# RPi_Rover_Hat.net
KiCad netlist of a schematic drawn in EAGLE
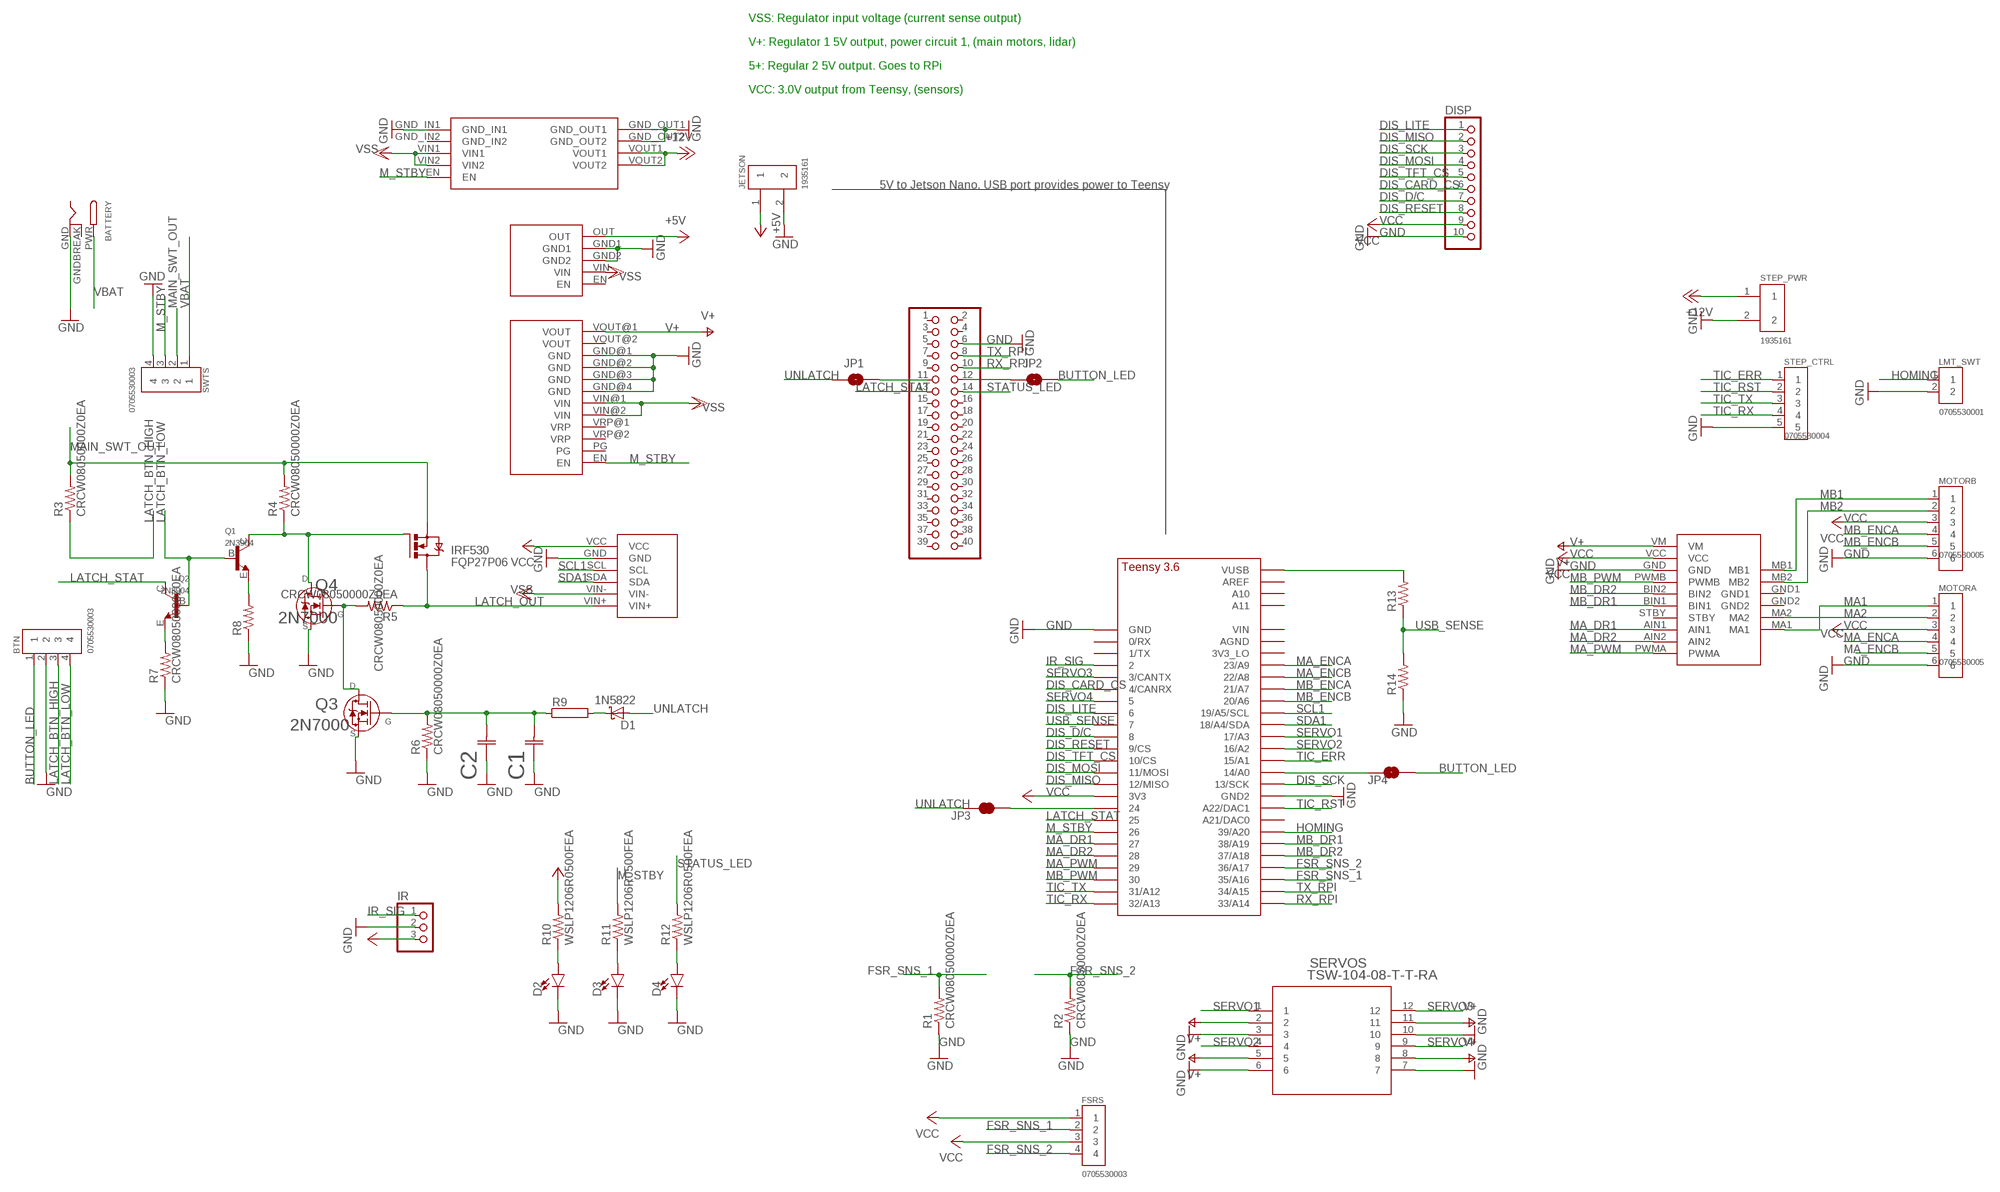
[diagram p0: schematic, sheet 1]

(export (version "E")
  (design (tool "Eeschema 10.0.6"))
  (components
    (comp (ref "BATTERY")
      (value "DCBARRELPTH")
      (footprint "eagle-import:DCJACK_2MM_PTH")
      (libsource (lib "eagle-import") (part "DCBARRELPTH"))
    )
    (comp (ref "BTN")
      (value "0705530003")
      (footprint "eagle-import:MOLEX_0705530003")
      (fields (field (name "DIGI-KEY_PART_NUMBER") "WM4902-ND") (field (name "MF") "Molex"))
      (libsource (lib "eagle-import") (part "0705530003"))
    )
    (comp (ref "C1")
      (value "FK24X5R0J226M")
      (footprint "eagle-import:CAP_R4525B")
      (libsource (lib "eagle-import") (part "FK24X5R0J226M"))
    )
    (comp (ref "C2")
      (value "FK24X5R0J226M")
      (footprint "eagle-import:CAP_R4525B")
      (libsource (lib "eagle-import") (part "FK24X5R0J226M"))
    )
    (comp (ref "D1")
      (value "1N5822")
      (footprint "eagle-import:DIOAD2120W130L950D530P")
      (fields (field (name "DIGI-KEY_PART_NUMBER") "1N5822FSCT-ND") (field (name "MF") "ON Semiconductor"))
      (libsource (lib "eagle-import") (part "1N5822"))
    )
    (comp (ref "D2")
      (value "LED1206")
      (footprint "eagle-import:LED-1206")
      (libsource (lib "eagle-import") (part "LED1206"))
    )
    (comp (ref "D3")
      (value "LED1206")
      (footprint "eagle-import:LED-1206")
      (libsource (lib "eagle-import") (part "LED1206"))
    )
    (comp (ref "D4")
      (value "LED1206")
      (footprint "eagle-import:LED-1206")
      (libsource (lib "eagle-import") (part "LED1206"))
    )
    (comp (ref "DISP")
      (value "PINHD-1X10")
      (footprint "eagle-import:1X10")
      (libsource (lib "eagle-import") (part "PINHD-1X10"))
    )
    (comp (ref "FQP27P06")
      (value "IRF530")
      (footprint "eagle-import:TO220BV")
      (fields (field (name "MF") "Vishay Siliconix"))
      (libsource (lib "eagle-import") (part "IRF530"))
    )
    (comp (ref "FSRS")
      (value "0705530003")
      (footprint "eagle-import:MOLEX_0705530003")
      (fields (field (name "DIGI-KEY_PART_NUMBER") "WM4902-ND") (field (name "MF") "Molex"))
      (libsource (lib "eagle-import") (part "0705530003"))
    )
    (comp (ref "IR")
      (value "PINHD-1X3")
      (footprint "eagle-import:1X03")
      (libsource (lib "eagle-import") (part "PINHD-1X3"))
    )
    (comp (ref "JETSON")
      (value "1935161")
      (footprint "eagle-import:PHOENIX_1935161")
      (fields (field (name "DIGI-KEY_PART_NUMBER") "277-1667-ND") (field (name "MF") "Phoenix Contact"))
      (libsource (lib "eagle-import") (part "1935161"))
    )
    (comp (ref "JP1")
      (value "JUMPER-SMT_2_NO_NO-SILK")
      (footprint "eagle-import:SMT-JUMPER_2_NO_NO-SILK")
      (libsource (lib "eagle-import") (part "JUMPER-SMT_2_NO_NO-SILK"))
    )
    (comp (ref "JP2")
      (value "JUMPER-SMT_2_NO_NO-SILK")
      (footprint "eagle-import:SMT-JUMPER_2_NO_NO-SILK")
      (libsource (lib "eagle-import") (part "JUMPER-SMT_2_NO_NO-SILK"))
    )
    (comp (ref "JP3")
      (value "JUMPER-SMT_2_NC_TRACE_NO-SILK")
      (footprint "eagle-import:SMT-JUMPER_2_NC_TRACE_NO-SILK")
      (libsource (lib "eagle-import") (part "JUMPER-SMT_2_NC_TRACE_NO-SILK"))
    )
    (comp (ref "JP4")
      (value "JUMPER-SMT_2_NC_TRACE_NO-SILK")
      (footprint "eagle-import:SMT-JUMPER_2_NC_TRACE_NO-SILK")
      (libsource (lib "eagle-import") (part "JUMPER-SMT_2_NC_TRACE_NO-SILK"))
    )
    (comp (ref "LMT_SWT")
      (value "0705530001")
      (footprint "eagle-import:MOLEX_0705530001")
      (libsource (lib "eagle-import") (part "0705530001"))
    )
    (comp (ref "MAIN_HEADER")
      (value "PINHD-2X20")
      (footprint "eagle-import:2X20")
      (libsource (lib "eagle-import") (part "PINHD-2X20"))
    )
    (comp (ref "MOTORA")
      (value "0705530005")
      (footprint "eagle-import:MOLEX_0705530005")
      (libsource (lib "eagle-import") (part "0705530005"))
    )
    (comp (ref "MOTORB")
      (value "0705530005")
      (footprint "eagle-import:MOLEX_0705530005")
      (libsource (lib "eagle-import") (part "0705530005"))
    )
    (comp (ref "Q1")
      (value "2N3904")
      (footprint "eagle-import:TO92")
      (libsource (lib "eagle-import") (part "2N3904"))
    )
    (comp (ref "Q2")
      (value "2N3904")
      (footprint "eagle-import:TO92")
      (libsource (lib "eagle-import") (part "2N3904"))
    )
    (comp (ref "Q3")
      (value "2N7000")
      (footprint "eagle-import:TO-92")
      (libsource (lib "eagle-import") (part "2N7000"))
    )
    (comp (ref "Q4")
      (value "2N7000")
      (footprint "eagle-import:TO-92")
      (libsource (lib "eagle-import") (part "2N7000"))
    )
    (comp (ref "R1")
      (value "CRCW08050000Z0EA")
      (footprint "eagle-import:RES_0805")
      (fields
        (field (name "DIGIKEY_PART_NUMBER") "541-0.0ATR-ND")
        (field (name "MANUFACTURER") "Vishay Dale")
        (field (name "CREATED_BY") "PCBLayout.com")
      )
      (libsource (lib "eagle-import") (part "CRCW08050000Z0EA"))
    )
    (comp (ref "R2")
      (value "CRCW08050000Z0EA")
      (footprint "eagle-import:RES_0805")
      (fields
        (field (name "DIGIKEY_PART_NUMBER") "541-0.0ATR-ND")
        (field (name "MANUFACTURER") "Vishay Dale")
        (field (name "CREATED_BY") "PCBLayout.com")
      )
      (libsource (lib "eagle-import") (part "CRCW08050000Z0EA"))
    )
    (comp (ref "R3")
      (value "CRCW08050000Z0EA")
      (footprint "eagle-import:RES_0805")
      (fields
        (field (name "DIGIKEY_PART_NUMBER") "541-0.0ATR-ND")
        (field (name "MANUFACTURER") "Vishay Dale")
        (field (name "CREATED_BY") "PCBLayout.com")
      )
      (libsource (lib "eagle-import") (part "CRCW08050000Z0EA"))
    )
    (comp (ref "R4")
      (value "CRCW08050000Z0EA")
      (footprint "eagle-import:RES_0805")
      (fields
        (field (name "DIGIKEY_PART_NUMBER") "541-0.0ATR-ND")
        (field (name "MANUFACTURER") "Vishay Dale")
        (field (name "CREATED_BY") "PCBLayout.com")
      )
      (libsource (lib "eagle-import") (part "CRCW08050000Z0EA"))
    )
    (comp (ref "R5")
      (value "CRCW08050000Z0EA")
      (footprint "eagle-import:RES_0805")
      (fields
        (field (name "DIGIKEY_PART_NUMBER") "541-0.0ATR-ND")
        (field (name "MANUFACTURER") "Vishay Dale")
        (field (name "CREATED_BY") "PCBLayout.com")
      )
      (libsource (lib "eagle-import") (part "CRCW08050000Z0EA"))
    )
    (comp (ref "R6")
      (value "CRCW08050000Z0EA")
      (footprint "eagle-import:RES_0805")
      (fields
        (field (name "DIGIKEY_PART_NUMBER") "541-0.0ATR-ND")
        (field (name "MANUFACTURER") "Vishay Dale")
        (field (name "CREATED_BY") "PCBLayout.com")
      )
      (libsource (lib "eagle-import") (part "CRCW08050000Z0EA"))
    )
    (comp (ref "R7")
      (value "CRCW08050000Z0EA")
      (footprint "eagle-import:RES_0805")
      (fields
        (field (name "DIGIKEY_PART_NUMBER") "541-0.0ATR-ND")
        (field (name "MANUFACTURER") "Vishay Dale")
        (field (name "CREATED_BY") "PCBLayout.com")
      )
      (libsource (lib "eagle-import") (part "CRCW08050000Z0EA"))
    )
    (comp (ref "R8")
      (value "CRCW08050000Z0EA")
      (footprint "eagle-import:RES_0805")
      (fields
        (field (name "DIGIKEY_PART_NUMBER") "541-0.0ATR-ND")
        (field (name "MANUFACTURER") "Vishay Dale")
        (field (name "CREATED_BY") "PCBLayout.com")
      )
      (libsource (lib "eagle-import") (part "CRCW08050000Z0EA"))
    )
    (comp (ref "R9")
      (value "RHPS58")
      (footprint "eagle-import:HPS58")
      (libsource (lib "eagle-import") (part "RHPS58"))
    )
    (comp (ref "R10")
      (value "WSLP1206R0500FEA")
      (footprint "eagle-import:RES_1206")
      (fields
        (field (name "DIGIKEY_PART_NUMBER") "WSLP-.05TR-ND")
        (field (name "MANUFACTURER") "Vishay Dale")
        (field (name "CREATED_BY") "PCBLayout.com")
      )
      (libsource (lib "eagle-import") (part "WSLP1206R0500FEA"))
    )
    (comp (ref "R11")
      (value "WSLP1206R0500FEA")
      (footprint "eagle-import:RES_1206")
      (fields
        (field (name "DIGIKEY_PART_NUMBER") "WSLP-.05TR-ND")
        (field (name "MANUFACTURER") "Vishay Dale")
        (field (name "CREATED_BY") "PCBLayout.com")
      )
      (libsource (lib "eagle-import") (part "WSLP1206R0500FEA"))
    )
    (comp (ref "R12")
      (value "WSLP1206R0500FEA")
      (footprint "eagle-import:RES_1206")
      (fields
        (field (name "DIGIKEY_PART_NUMBER") "WSLP-.05TR-ND")
        (field (name "MANUFACTURER") "Vishay Dale")
        (field (name "CREATED_BY") "PCBLayout.com")
      )
      (libsource (lib "eagle-import") (part "WSLP1206R0500FEA"))
    )
    (comp (ref "R13")
      (value "CRCW08050000Z0EA")
      (footprint "eagle-import:RES_0805")
      (fields
        (field (name "DIGIKEY_PART_NUMBER") "541-0.0ATR-ND")
        (field (name "MANUFACTURER") "Vishay Dale")
        (field (name "CREATED_BY") "PCBLayout.com")
      )
      (libsource (lib "eagle-import") (part "CRCW08050000Z0EA"))
    )
    (comp (ref "R14")
      (value "CRCW08050000Z0EA")
      (footprint "eagle-import:RES_0805")
      (fields
        (field (name "DIGIKEY_PART_NUMBER") "541-0.0ATR-ND")
        (field (name "MANUFACTURER") "Vishay Dale")
        (field (name "CREATED_BY") "PCBLayout.com")
      )
      (libsource (lib "eagle-import") (part "CRCW08050000Z0EA"))
    )
    (comp (ref "SERVOS")
      (value "TSW-104-08-T-T-RA")
      (footprint "eagle-import:TSW-104-08-T-T-RA_SAI")
      (libsource (lib "eagle-import") (part "TSW-104-08-T-T-RA"))
    )
    (comp (ref "STEP_CTRL")
      (value "0705530004")
      (footprint "eagle-import:MOLEX_0705530004")
      (libsource (lib "eagle-import") (part "0705530004"))
    )
    (comp (ref "STEP_PWR")
      (value "1935161")
      (footprint "eagle-import:PHOENIX_1935161")
      (fields (field (name "DIGI-KEY_PART_NUMBER") "277-1667-ND") (field (name "MF") "Phoenix Contact"))
      (libsource (lib "eagle-import") (part "1935161"))
    )
    (comp (ref "SWTS")
      (value "0705530003")
      (footprint "eagle-import:MOLEX_0705530003")
      (fields (field (name "DIGI-KEY_PART_NUMBER") "WM4902-ND") (field (name "MF") "Molex"))
      (libsource (lib "eagle-import") (part "0705530003"))
    )
    (comp (ref "U$1")
      (value "TEENSY_3.5/3.6_BASIC")
      (footprint "eagle-import:TEENSY_3.5_3.6_BASIC")
      (libsource (lib "eagle-import") (part "TEENSY_3.5/3.6_BASIC"))
    )
    (comp (ref "U$3")
      (value "ADAFRUIT_TB6612")
      (footprint "eagle-import:ADAFRUIT_TB6612")
      (libsource (lib "eagle-import") (part "ADAFRUIT_TB6612"))
    )
    (comp (ref "U$4")
      (value "INA219")
      (footprint "eagle-import:INA219")
      (libsource (lib "eagle-import") (part "INA219"))
    )
    (comp (ref "U$5")
      (value "D24V50F5")
      (footprint "eagle-import:D24V50F5")
      (libsource (lib "eagle-import") (part "D24V50F5"))
    )
    (comp (ref "U$6")
      (value "S18V20FX")
      (footprint "eagle-import:S18V20FX")
      (libsource (lib "eagle-import") (part "S18V20FX"))
    )
    (comp (ref "U$7")
      (value "D36V50FX")
      (footprint "eagle-import:D36V50FX")
      (libsource (lib "eagle-import") (part "D36V50FX"))
    )
  )
  (nets
    (net (code "1") (name "+5V") (class "Default")
      (node (ref "JETSON") (pin "1") (pinfunction "1_1") (pintype "passive"))
      (node (ref "U$5") (pin "OUT") (pinfunction "OUT_OUT") (pintype "bidirectional"))
    )
    (net (code "2") (name "+12V") (class "Default")
      (node (ref "STEP_PWR") (pin "1") (pinfunction "1_1") (pintype "passive"))
      (node (ref "U$6") (pin "VOUT1") (pinfunction "VOUT1_VOUT1") (pintype "bidirectional"))
      (node (ref "U$6") (pin "VOUT2") (pinfunction "VOUT2_VOUT2") (pintype "bidirectional"))
    )
    (net (code "3") (name "/BUTTON_LED") (class "Default")
      (node (ref "BTN") (pin "1") (pinfunction "1_1") (pintype "passive"))
      (node (ref "JP2") (pin "2") (pinfunction "2_2") (pintype "passive"))
      (node (ref "JP4") (pin "2") (pinfunction "2_2") (pintype "passive"))
    )
    (net (code "4") (name "/DIS_CARD_CS") (class "Default")
      (node (ref "DISP") (pin "6") (pinfunction "6_6") (pintype "passive"))
      (node (ref "U$1") (pin "4/CANRX") (pinfunction "4/CANRX_4/CANRX") (pintype "bidirectional"))
    )
    (net (code "5") (name "/DIS_D{slash}C") (class "Default")
      (node (ref "DISP") (pin "7") (pinfunction "7_7") (pintype "passive"))
      (node (ref "U$1") (pin "8") (pinfunction "8_8") (pintype "bidirectional"))
    )
    (net (code "6") (name "/DIS_LITE") (class "Default")
      (node (ref "DISP") (pin "1") (pinfunction "1_1") (pintype "passive"))
      (node (ref "U$1") (pin "6") (pinfunction "6_6") (pintype "bidirectional"))
    )
    (net (code "7") (name "/DIS_MISO") (class "Default")
      (node (ref "DISP") (pin "2") (pinfunction "2_2") (pintype "passive"))
      (node (ref "U$1") (pin "12/MISO") (pinfunction "12/MISO_12/MISO") (pintype "bidirectional"))
    )
    (net (code "8") (name "/DIS_MOSI") (class "Default")
      (node (ref "DISP") (pin "4") (pinfunction "4_4") (pintype "passive"))
      (node (ref "U$1") (pin "11/MOSI") (pinfunction "11/MOSI_11/MOSI") (pintype "bidirectional"))
    )
    (net (code "9") (name "/DIS_RESET") (class "Default")
      (node (ref "DISP") (pin "8") (pinfunction "8_8") (pintype "passive"))
      (node (ref "U$1") (pin "9/CS") (pinfunction "9/CS_9/CS") (pintype "bidirectional"))
    )
    (net (code "10") (name "/DIS_SCK") (class "Default")
      (node (ref "DISP") (pin "3") (pinfunction "3_3") (pintype "passive"))
      (node (ref "U$1") (pin "13/SCK") (pinfunction "13/SCK_13/SCK") (pintype "bidirectional"))
    )
    (net (code "11") (name "/DIS_TFT_CS") (class "Default")
      (node (ref "DISP") (pin "5") (pinfunction "5_5") (pintype "passive"))
      (node (ref "U$1") (pin "10/CS") (pinfunction "10/CS_10/CS") (pintype "bidirectional"))
    )
    (net (code "12") (name "/FSR_SNS_1") (class "Default")
      (node (ref "FSRS") (pin "2") (pinfunction "2_2") (pintype "passive"))
      (node (ref "R1") (pin "2") (pinfunction "2_2") (pintype "passive"))
      (node (ref "U$1") (pin "35/A16") (pinfunction "35/A16_35/A16") (pintype "bidirectional"))
    )
    (net (code "13") (name "/FSR_SNS_2") (class "Default")
      (node (ref "FSRS") (pin "4") (pinfunction "4_4") (pintype "passive"))
      (node (ref "R2") (pin "2") (pinfunction "2_2") (pintype "passive"))
      (node (ref "U$1") (pin "36/A17") (pinfunction "36/A17_36/A17") (pintype "bidirectional"))
    )
    (net (code "14") (name "/GNDBREAK") (class "Default")
      (node (ref "BATTERY") (pin "GNDBREAK") (pinfunction "GNDBREAK_GNDBREAK") (pintype "power_in"))
    )
    (net (code "15") (name "/HOMING") (class "Default")
      (node (ref "LMT_SWT") (pin "1") (pinfunction "1_1") (pintype "passive"))
      (node (ref "U$1") (pin "39/A20") (pinfunction "39/A20_39/A20") (pintype "bidirectional"))
    )
    (net (code "16") (name "/IR_SIG") (class "Default")
      (node (ref "IR") (pin "1") (pinfunction "1_1") (pintype "passive"))
      (node (ref "U$1") (pin "2") (pinfunction "2_2") (pintype "bidirectional"))
    )
    (net (code "17") (name "/LATCH_BTN_HIGH") (class "Default")
      (node (ref "BTN") (pin "3") (pinfunction "3_3") (pintype "passive"))
      (node (ref "R3") (pin "1") (pinfunction "1_1") (pintype "passive"))
    )
    (net (code "18") (name "/LATCH_BTN_LOW") (class "Default")
      (node (ref "BTN") (pin "4") (pinfunction "4_4") (pintype "passive"))
      (node (ref "Q1") (pin "B") (pinfunction "B_B") (pintype "passive"))
      (node (ref "Q2") (pin "B") (pinfunction "B_B") (pintype "passive"))
    )
    (net (code "19") (name "/LATCH_OUT") (class "Default")
      (node (ref "FQP27P06") (pin "D") (pinfunction "D_D") (pintype "passive"))
      (node (ref "R5") (pin "1") (pinfunction "1_1") (pintype "passive"))
      (node (ref "U$4") (pin "VIN+") (pinfunction "VIN+_VIN+") (pintype "bidirectional"))
    )
    (net (code "20") (name "/LATCH_STAT") (class "Default")
      (node (ref "MAIN_HEADER") (pin "13") (pinfunction "13_13") (pintype "passive"))
      (node (ref "Q2") (pin "C") (pinfunction "C_C") (pintype "passive"))
      (node (ref "U$1") (pin "25") (pinfunction "25_25") (pintype "bidirectional"))
    )
    (net (code "21") (name "/MA1") (class "Default")
      (node (ref "MOTORA") (pin "1") (pinfunction "1_1") (pintype "passive"))
      (node (ref "U$3") (pin "MA1") (pinfunction "MA1_MA1") (pintype "bidirectional"))
    )
    (net (code "22") (name "/MA2") (class "Default")
      (node (ref "MOTORA") (pin "2") (pinfunction "2_2") (pintype "passive"))
      (node (ref "U$3") (pin "MA2") (pinfunction "MA2_MA2") (pintype "bidirectional"))
    )
    (net (code "23") (name "/MAIN_SWT_OUT") (class "Default")
      (node (ref "FQP27P06") (pin "S") (pinfunction "S_S") (pintype "passive"))
      (node (ref "R3") (pin "2") (pinfunction "2_2") (pintype "passive"))
      (node (ref "R4") (pin "2") (pinfunction "2_2") (pintype "passive"))
      (node (ref "SWTS") (pin "2") (pinfunction "2_2") (pintype "passive"))
    )
    (net (code "24") (name "/MA_DR1") (class "Default")
      (node (ref "U$1") (pin "27") (pinfunction "27_27") (pintype "bidirectional"))
      (node (ref "U$3") (pin "AIN1") (pinfunction "AIN1_AIN1") (pintype "bidirectional"))
    )
    (net (code "25") (name "/MA_DR2") (class "Default")
      (node (ref "U$1") (pin "28") (pinfunction "28_28") (pintype "bidirectional"))
      (node (ref "U$3") (pin "AIN2") (pinfunction "AIN2_AIN2") (pintype "bidirectional"))
    )
    (net (code "26") (name "/MA_ENCA") (class "Default")
      (node (ref "MOTORA") (pin "4") (pinfunction "4_4") (pintype "passive"))
      (node (ref "U$1") (pin "23/A9") (pinfunction "23/A9_23/A9") (pintype "bidirectional"))
    )
    (net (code "27") (name "/MA_ENCB") (class "Default")
      (node (ref "MOTORA") (pin "5") (pinfunction "5_5") (pintype "passive"))
      (node (ref "U$1") (pin "22/A8") (pinfunction "22/A8_22/A8") (pintype "bidirectional"))
    )
    (net (code "28") (name "/MA_PWM") (class "Default")
      (node (ref "U$1") (pin "29") (pinfunction "29_29") (pintype "bidirectional"))
      (node (ref "U$3") (pin "PWMA") (pinfunction "PWMA_PWMA") (pintype "bidirectional"))
    )
    (net (code "29") (name "/MB1") (class "Default")
      (node (ref "MOTORB") (pin "1") (pinfunction "1_1") (pintype "passive"))
      (node (ref "U$3") (pin "MB1") (pinfunction "MB1_MB1") (pintype "bidirectional"))
    )
    (net (code "30") (name "/MB2") (class "Default")
      (node (ref "MOTORB") (pin "2") (pinfunction "2_2") (pintype "passive"))
      (node (ref "U$3") (pin "MB2") (pinfunction "MB2_MB2") (pintype "bidirectional"))
    )
    (net (code "31") (name "/MB_DR1") (class "Default")
      (node (ref "U$1") (pin "38/A19") (pinfunction "38/A19_38/A19") (pintype "bidirectional"))
      (node (ref "U$3") (pin "BIN1") (pinfunction "BIN1_BIN1") (pintype "bidirectional"))
    )
    (net (code "32") (name "/MB_DR2") (class "Default")
      (node (ref "U$1") (pin "37/A18") (pinfunction "37/A18_37/A18") (pintype "bidirectional"))
      (node (ref "U$3") (pin "BIN2") (pinfunction "BIN2_BIN2") (pintype "bidirectional"))
    )
    (net (code "33") (name "/MB_ENCA") (class "Default")
      (node (ref "MOTORB") (pin "4") (pinfunction "4_4") (pintype "passive"))
      (node (ref "U$1") (pin "21/A7") (pinfunction "21/A7_21/A7") (pintype "bidirectional"))
    )
    (net (code "34") (name "/MB_ENCB") (class "Default")
      (node (ref "MOTORB") (pin "5") (pinfunction "5_5") (pintype "passive"))
      (node (ref "U$1") (pin "20/A6") (pinfunction "20/A6_20/A6") (pintype "bidirectional"))
    )
    (net (code "35") (name "/MB_PWM") (class "Default")
      (node (ref "U$1") (pin "30") (pinfunction "30_30") (pintype "bidirectional"))
      (node (ref "U$3") (pin "PWMB") (pinfunction "PWMB_PWMB") (pintype "bidirectional"))
    )
    (net (code "36") (name "/M_STBY") (class "Default")
      (node (ref "R11") (pin "2") (pinfunction "2_2") (pintype "passive"))
      (node (ref "SWTS") (pin "3") (pinfunction "3_3") (pintype "passive"))
      (node (ref "U$1") (pin "26") (pinfunction "26_26") (pintype "bidirectional"))
      (node (ref "U$6") (pin "EN") (pinfunction "EN_EN") (pintype "bidirectional"))
      (node (ref "U$7") (pin "EN") (pinfunction "EN_EN") (pintype "bidirectional"))
    )
    (net (code "37") (name "/RX_RPI") (class "Default")
      (node (ref "MAIN_HEADER") (pin "10") (pinfunction "10_10") (pintype "passive"))
      (node (ref "U$1") (pin "33/A14") (pinfunction "33/A14_33/A14") (pintype "bidirectional"))
    )
    (net (code "38") (name "/SCL1") (class "Default")
      (node (ref "U$1") (pin "19/A5/SCL") (pinfunction "19/A5/SCL_19/A5/SCL") (pintype "bidirectional"))
      (node (ref "U$4") (pin "SCL") (pinfunction "SCL_SCL") (pintype "bidirectional"))
    )
    (net (code "39") (name "/SDA1") (class "Default")
      (node (ref "U$1") (pin "18/A4/SDA") (pinfunction "18/A4/SDA_18/A4/SDA") (pintype "bidirectional"))
      (node (ref "U$4") (pin "SDA") (pinfunction "SDA_SDA") (pintype "bidirectional"))
    )
    (net (code "40") (name "/SERVO1") (class "Default")
      (node (ref "SERVOS") (pin "1") (pinfunction "1_1") (pintype "passive"))
      (node (ref "U$1") (pin "17/A3") (pinfunction "17/A3_17/A3") (pintype "bidirectional"))
    )
    (net (code "41") (name "/SERVO2") (class "Default")
      (node (ref "SERVOS") (pin "4") (pinfunction "4_4") (pintype "passive"))
      (node (ref "U$1") (pin "16/A2") (pinfunction "16/A2_16/A2") (pintype "bidirectional"))
    )
    (net (code "42") (name "/SERVO3") (class "Default")
      (node (ref "SERVOS") (pin "12") (pinfunction "12_12") (pintype "passive"))
      (node (ref "U$1") (pin "3/CANTX") (pinfunction "3/CANTX_3/CANTX") (pintype "bidirectional"))
    )
    (net (code "43") (name "/SERVO4") (class "Default")
      (node (ref "SERVOS") (pin "9") (pinfunction "9_9") (pintype "passive"))
      (node (ref "U$1") (pin "5") (pinfunction "5_5") (pintype "bidirectional"))
    )
    (net (code "44") (name "/STATUS_LED") (class "Default")
      (node (ref "MAIN_HEADER") (pin "14") (pinfunction "14_14") (pintype "passive"))
      (node (ref "R12") (pin "2") (pinfunction "2_2") (pintype "passive"))
    )
    (net (code "45") (name "/TIC_ERR") (class "Default")
      (node (ref "STEP_CTRL") (pin "1") (pinfunction "1_1") (pintype "passive"))
      (node (ref "U$1") (pin "15/A1") (pinfunction "15/A1_15/A1") (pintype "bidirectional"))
    )
    (net (code "46") (name "/TIC_RST") (class "Default")
      (node (ref "STEP_CTRL") (pin "2") (pinfunction "2_2") (pintype "passive"))
      (node (ref "U$1") (pin "A22/DAC1") (pinfunction "A22/DAC1_A22/DAC1") (pintype "bidirectional"))
    )
    (net (code "47") (name "/TIC_RX") (class "Default")
      (node (ref "STEP_CTRL") (pin "4") (pinfunction "4_4") (pintype "passive"))
      (node (ref "U$1") (pin "32/A13") (pinfunction "32/A13_32/A13") (pintype "bidirectional"))
    )
    (net (code "48") (name "/TIC_TX") (class "Default")
      (node (ref "STEP_CTRL") (pin "3") (pinfunction "3_3") (pintype "passive"))
      (node (ref "U$1") (pin "31/A12") (pinfunction "31/A12_31/A12") (pintype "bidirectional"))
    )
    (net (code "49") (name "/TX_RPI") (class "Default")
      (node (ref "MAIN_HEADER") (pin "8") (pinfunction "8_8") (pintype "passive"))
      (node (ref "U$1") (pin "34/A15") (pinfunction "34/A15_34/A15") (pintype "bidirectional"))
    )
    (net (code "50") (name "/UNLATCH") (class "Default")
      (node (ref "D1") (pin "A") (pinfunction "A_A") (pintype "passive"))
      (node (ref "JP1") (pin "1") (pinfunction "1_1") (pintype "passive"))
      (node (ref "JP3") (pin "1") (pinfunction "1_1") (pintype "passive"))
    )
    (net (code "51") (name "/USB_SENSE") (class "Default")
      (node (ref "R13") (pin "1") (pinfunction "1_1") (pintype "passive"))
      (node (ref "R14") (pin "2") (pinfunction "2_2") (pintype "passive"))
      (node (ref "U$1") (pin "7") (pinfunction "7_7") (pintype "bidirectional"))
    )
    (net (code "52") (name "/VBAT") (class "Default")
      (node (ref "BATTERY") (pin "PWR") (pinfunction "PWR_PWR") (pintype "power_in"))
      (node (ref "SWTS") (pin "1") (pinfunction "1_1") (pintype "passive"))
    )
    (net (code "53") (name "GND") (class "Default")
      (node (ref "BATTERY") (pin "GND") (pinfunction "GND_GND") (pintype "power_in"))
      (node (ref "BTN") (pin "2") (pinfunction "2_2") (pintype "passive"))
      (node (ref "C1") (pin "1") (pinfunction "1_1") (pintype "passive"))
      (node (ref "C2") (pin "1") (pinfunction "1_1") (pintype "passive"))
      (node (ref "D2") (pin "C") (pinfunction "C_C") (pintype "passive"))
      (node (ref "D3") (pin "C") (pinfunction "C_C") (pintype "passive"))
      (node (ref "D4") (pin "C") (pinfunction "C_C") (pintype "passive"))
      (node (ref "DISP") (pin "10") (pinfunction "10_10") (pintype "passive"))
      (node (ref "IR") (pin "2") (pinfunction "2_2") (pintype "passive"))
      (node (ref "JETSON") (pin "2") (pinfunction "2_2") (pintype "passive"))
      (node (ref "LMT_SWT") (pin "2") (pinfunction "2_2") (pintype "passive"))
      (node (ref "MAIN_HEADER") (pin "6") (pinfunction "6_6") (pintype "passive"))
      (node (ref "MOTORA") (pin "6") (pinfunction "6_6") (pintype "passive"))
      (node (ref "MOTORB") (pin "6") (pinfunction "6_6") (pintype "passive"))
      (node (ref "Q3") (pin "1") (pinfunction "3_1") (pintype "passive"))
      (node (ref "Q4") (pin "1") (pinfunction "3_1") (pintype "passive"))
      (node (ref "R1") (pin "1") (pinfunction "1_1") (pintype "passive"))
      (node (ref "R14") (pin "1") (pinfunction "1_1") (pintype "passive"))
      (node (ref "R2") (pin "1") (pinfunction "1_1") (pintype "passive"))
      (node (ref "R6") (pin "1") (pinfunction "1_1") (pintype "passive"))
      (node (ref "R7") (pin "1") (pinfunction "1_1") (pintype "passive"))
      (node (ref "R8") (pin "1") (pinfunction "1_1") (pintype "passive"))
      (node (ref "SERVOS") (pin "10") (pinfunction "10_10") (pintype "passive"))
      (node (ref "SERVOS") (pin "3") (pinfunction "3_3") (pintype "passive"))
      (node (ref "SERVOS") (pin "6") (pinfunction "6_6") (pintype "passive"))
      (node (ref "SERVOS") (pin "7") (pinfunction "7_7") (pintype "passive"))
      (node (ref "STEP_CTRL") (pin "5") (pinfunction "5_5") (pintype "passive"))
      (node (ref "STEP_PWR") (pin "2") (pinfunction "2_2") (pintype "passive"))
      (node (ref "SWTS") (pin "4") (pinfunction "4_4") (pintype "passive"))
      (node (ref "U$1") (pin "GND") (pinfunction "GND_GND") (pintype "bidirectional"))
      (node (ref "U$1") (pin "GND2") (pinfunction "GND2_GND2") (pintype "bidirectional"))
      (node (ref "U$3") (pin "GND") (pinfunction "GND_GND") (pintype "bidirectional"))
      (node (ref "U$4") (pin "GND") (pinfunction "GND_GND") (pintype "bidirectional"))
      (node (ref "U$5") (pin "GND1") (pinfunction "GND1_GND1") (pintype "bidirectional"))
      (node (ref "U$5") (pin "GND2") (pinfunction "GND2_GND2") (pintype "bidirectional"))
      (node (ref "U$6") (pin "GND_IN1") (pinfunction "GND_IN1_GND_IN1") (pintype "bidirectional"))
      (node (ref "U$6") (pin "GND_OUT1") (pinfunction "GND_OUT1_GND_OUT1") (pintype "bidirectional"))
      (node (ref "U$6") (pin "GND_OUT2") (pinfunction "GND_OUT2_GND_OUT2") (pintype "bidirectional"))
      (node (ref "U$7") (pin "GND@1") (pinfunction "GND_GND@1") (pintype "bidirectional"))
      (node (ref "U$7") (pin "GND@2") (pinfunction "GND_GND@2") (pintype "bidirectional"))
      (node (ref "U$7") (pin "GND@3") (pinfunction "GND_GND@3") (pintype "bidirectional"))
      (node (ref "U$7") (pin "GND@4") (pinfunction "GND_GND@4") (pintype "bidirectional"))
    )
    (net (code "54") (name "Net-(D1-PadC)") (class "Default")
      (node (ref "D1") (pin "C") (pinfunction "C_C") (pintype "passive"))
      (node (ref "R9") (pin "2") (pinfunction "2_2") (pintype "passive"))
    )
    (net (code "55") (name "Net-(D2-PadA)") (class "Default")
      (node (ref "D2") (pin "A") (pinfunction "A_A") (pintype "passive"))
      (node (ref "R10") (pin "1") (pinfunction "1_1") (pintype "passive"))
    )
    (net (code "56") (name "Net-(D3-PadA)") (class "Default")
      (node (ref "D3") (pin "A") (pinfunction "A_A") (pintype "passive"))
      (node (ref "R11") (pin "1") (pinfunction "1_1") (pintype "passive"))
    )
    (net (code "57") (name "Net-(D4-PadA)") (class "Default")
      (node (ref "D4") (pin "A") (pinfunction "A_A") (pintype "passive"))
      (node (ref "R12") (pin "1") (pinfunction "1_1") (pintype "passive"))
    )
    (net (code "58") (name "Net-(JP1-Pad2)") (class "Default")
      (node (ref "JP1") (pin "2") (pinfunction "2_2") (pintype "passive"))
      (node (ref "MAIN_HEADER") (pin "11") (pinfunction "11_11") (pintype "passive"))
    )
    (net (code "59") (name "Net-(JP2-Pad1)") (class "Default")
      (node (ref "JP2") (pin "1") (pinfunction "1_1") (pintype "passive"))
      (node (ref "MAIN_HEADER") (pin "12") (pinfunction "12_12") (pintype "passive"))
    )
    (net (code "60") (name "Net-(JP3-Pad2)") (class "Default")
      (node (ref "JP3") (pin "2") (pinfunction "2_2") (pintype "passive"))
      (node (ref "U$1") (pin "24") (pinfunction "24_24") (pintype "bidirectional"))
    )
    (net (code "61") (name "Net-(JP4-Pad1)") (class "Default")
      (node (ref "JP4") (pin "1") (pinfunction "1_1") (pintype "passive"))
      (node (ref "U$1") (pin "14/A0") (pinfunction "14/A0_14/A0") (pintype "bidirectional"))
    )
    (net (code "62") (name "Net-(Q1-PadE)") (class "Default")
      (node (ref "Q1") (pin "E") (pinfunction "E_E") (pintype "passive"))
      (node (ref "R8") (pin "2") (pinfunction "2_2") (pintype "passive"))
    )
    (net (code "63") (name "Net-(Q2-PadE)") (class "Default")
      (node (ref "Q2") (pin "E") (pinfunction "E_E") (pintype "passive"))
      (node (ref "R7") (pin "2") (pinfunction "2_2") (pintype "passive"))
    )
    (net (code "64") (name "Net-(Q3-1)") (class "Default")
      (node (ref "C1") (pin "2") (pinfunction "2_2") (pintype "passive"))
      (node (ref "C2") (pin "2") (pinfunction "2_2") (pintype "passive"))
      (node (ref "Q3") (pin "2") (pinfunction "1_2") (pintype "passive"))
      (node (ref "R6") (pin "2") (pinfunction "2_2") (pintype "passive"))
      (node (ref "R9") (pin "1") (pinfunction "1_1") (pintype "passive"))
    )
    (net (code "65") (name "Net-(Q3-2)") (class "Default")
      (node (ref "Q3") (pin "3") (pinfunction "2_3") (pintype "passive"))
      (node (ref "Q4") (pin "2") (pinfunction "1_2") (pintype "passive"))
      (node (ref "R5") (pin "2") (pinfunction "2_2") (pintype "passive"))
    )
    (net (code "66") (name "Net-(Q4-2)") (class "Default")
      (node (ref "FQP27P06") (pin "G") (pinfunction "G_G") (pintype "passive"))
      (node (ref "Q1") (pin "C") (pinfunction "C_C") (pintype "passive"))
      (node (ref "Q4") (pin "3") (pinfunction "2_3") (pintype "passive"))
      (node (ref "R4") (pin "1") (pinfunction "1_1") (pintype "passive"))
    )
    (net (code "67") (name "Net-(R13-Pad2)") (class "Default")
      (node (ref "R13") (pin "2") (pinfunction "2_2") (pintype "passive"))
      (node (ref "U$1") (pin "VUSB") (pinfunction "VUSB_VUSB") (pintype "bidirectional"))
    )
    (net (code "68") (name "V+") (class "Default")
      (node (ref "SERVOS") (pin "11") (pinfunction "11_11") (pintype "passive"))
      (node (ref "SERVOS") (pin "2") (pinfunction "2_2") (pintype "passive"))
      (node (ref "SERVOS") (pin "5") (pinfunction "5_5") (pintype "passive"))
      (node (ref "SERVOS") (pin "8") (pinfunction "8_8") (pintype "passive"))
      (node (ref "U$3") (pin "VM") (pinfunction "VM_VM") (pintype "bidirectional"))
      (node (ref "U$7") (pin "VOUT@1") (pinfunction "VOUT_VOUT@1") (pintype "bidirectional"))
    )
    (net (code "69") (name "VCC") (class "Default")
      (node (ref "DISP") (pin "9") (pinfunction "9_9") (pintype "passive"))
      (node (ref "FSRS") (pin "1") (pinfunction "1_1") (pintype "passive"))
      (node (ref "FSRS") (pin "3") (pinfunction "3_3") (pintype "passive"))
      (node (ref "IR") (pin "3") (pinfunction "3_3") (pintype "passive"))
      (node (ref "MOTORA") (pin "3") (pinfunction "3_3") (pintype "passive"))
      (node (ref "MOTORB") (pin "3") (pinfunction "3_3") (pintype "passive"))
      (node (ref "R10") (pin "2") (pinfunction "2_2") (pintype "passive"))
      (node (ref "U$1") (pin "3V3") (pinfunction "3V3_3V3") (pintype "bidirectional"))
      (node (ref "U$3") (pin "VCC") (pinfunction "VCC_VCC") (pintype "bidirectional"))
      (node (ref "U$4") (pin "VCC") (pinfunction "VCC_VCC") (pintype "bidirectional"))
    )
    (net (code "70") (name "VSS") (class "Default")
      (node (ref "U$4") (pin "VIN-") (pinfunction "VIN-_VIN-") (pintype "bidirectional"))
      (node (ref "U$5") (pin "VIN") (pinfunction "VIN_VIN") (pintype "bidirectional"))
      (node (ref "U$6") (pin "VIN1") (pinfunction "VIN1_VIN1") (pintype "bidirectional"))
      (node (ref "U$6") (pin "VIN2") (pinfunction "VIN2_VIN2") (pintype "bidirectional"))
      (node (ref "U$7") (pin "VIN@1") (pinfunction "VIN_VIN@1") (pintype "bidirectional"))
      (node (ref "U$7") (pin "VIN@2") (pinfunction "VIN_VIN@2") (pintype "bidirectional"))
    )
    (net (code "71") (name "unconnected-(MAIN_HEADER-Pad1)") (class "Default")
      (node (ref "MAIN_HEADER") (pin "1") (pinfunction "1_1") (pintype "passive"))
    )
    (net (code "72") (name "unconnected-(MAIN_HEADER-Pad2)") (class "Default")
      (node (ref "MAIN_HEADER") (pin "2") (pinfunction "2_2") (pintype "passive"))
    )
    (net (code "73") (name "unconnected-(MAIN_HEADER-Pad3)") (class "Default")
      (node (ref "MAIN_HEADER") (pin "3") (pinfunction "3_3") (pintype "passive"))
    )
    (net (code "74") (name "unconnected-(MAIN_HEADER-Pad4)") (class "Default")
      (node (ref "MAIN_HEADER") (pin "4") (pinfunction "4_4") (pintype "passive"))
    )
    (net (code "75") (name "unconnected-(MAIN_HEADER-Pad5)") (class "Default")
      (node (ref "MAIN_HEADER") (pin "5") (pinfunction "5_5") (pintype "passive"))
    )
    (net (code "76") (name "unconnected-(MAIN_HEADER-Pad7)") (class "Default")
      (node (ref "MAIN_HEADER") (pin "7") (pinfunction "7_7") (pintype "passive"))
    )
    (net (code "77") (name "unconnected-(MAIN_HEADER-Pad9)") (class "Default")
      (node (ref "MAIN_HEADER") (pin "9") (pinfunction "9_9") (pintype "passive"))
    )
    (net (code "78") (name "unconnected-(MAIN_HEADER-Pad15)") (class "Default")
      (node (ref "MAIN_HEADER") (pin "15") (pinfunction "15_15") (pintype "passive"))
    )
    (net (code "79") (name "unconnected-(MAIN_HEADER-Pad16)") (class "Default")
      (node (ref "MAIN_HEADER") (pin "16") (pinfunction "16_16") (pintype "passive"))
    )
    (net (code "80") (name "unconnected-(MAIN_HEADER-Pad17)") (class "Default")
      (node (ref "MAIN_HEADER") (pin "17") (pinfunction "17_17") (pintype "passive"))
    )
    (net (code "81") (name "unconnected-(MAIN_HEADER-Pad18)") (class "Default")
      (node (ref "MAIN_HEADER") (pin "18") (pinfunction "18_18") (pintype "passive"))
    )
    (net (code "82") (name "unconnected-(MAIN_HEADER-Pad19)") (class "Default")
      (node (ref "MAIN_HEADER") (pin "19") (pinfunction "19_19") (pintype "passive"))
    )
    (net (code "83") (name "unconnected-(MAIN_HEADER-Pad20)") (class "Default")
      (node (ref "MAIN_HEADER") (pin "20") (pinfunction "20_20") (pintype "passive"))
    )
    (net (code "84") (name "unconnected-(MAIN_HEADER-Pad21)") (class "Default")
      (node (ref "MAIN_HEADER") (pin "21") (pinfunction "21_21") (pintype "passive"))
    )
    (net (code "85") (name "unconnected-(MAIN_HEADER-Pad22)") (class "Default")
      (node (ref "MAIN_HEADER") (pin "22") (pinfunction "22_22") (pintype "passive"))
    )
    (net (code "86") (name "unconnected-(MAIN_HEADER-Pad23)") (class "Default")
      (node (ref "MAIN_HEADER") (pin "23") (pinfunction "23_23") (pintype "passive"))
    )
    (net (code "87") (name "unconnected-(MAIN_HEADER-Pad24)") (class "Default")
      (node (ref "MAIN_HEADER") (pin "24") (pinfunction "24_24") (pintype "passive"))
    )
    (net (code "88") (name "unconnected-(MAIN_HEADER-Pad25)") (class "Default")
      (node (ref "MAIN_HEADER") (pin "25") (pinfunction "25_25") (pintype "passive"))
    )
    (net (code "89") (name "unconnected-(MAIN_HEADER-Pad26)") (class "Default")
      (node (ref "MAIN_HEADER") (pin "26") (pinfunction "26_26") (pintype "passive"))
    )
    (net (code "90") (name "unconnected-(MAIN_HEADER-Pad27)") (class "Default")
      (node (ref "MAIN_HEADER") (pin "27") (pinfunction "27_27") (pintype "passive"))
    )
    (net (code "91") (name "unconnected-(MAIN_HEADER-Pad28)") (class "Default")
      (node (ref "MAIN_HEADER") (pin "28") (pinfunction "28_28") (pintype "passive"))
    )
    (net (code "92") (name "unconnected-(MAIN_HEADER-Pad29)") (class "Default")
      (node (ref "MAIN_HEADER") (pin "29") (pinfunction "29_29") (pintype "passive"))
    )
    (net (code "93") (name "unconnected-(MAIN_HEADER-Pad30)") (class "Default")
      (node (ref "MAIN_HEADER") (pin "30") (pinfunction "30_30") (pintype "passive"))
    )
    (net (code "94") (name "unconnected-(MAIN_HEADER-Pad31)") (class "Default")
      (node (ref "MAIN_HEADER") (pin "31") (pinfunction "31_31") (pintype "passive"))
    )
    (net (code "95") (name "unconnected-(MAIN_HEADER-Pad32)") (class "Default")
      (node (ref "MAIN_HEADER") (pin "32") (pinfunction "32_32") (pintype "passive"))
    )
    (net (code "96") (name "unconnected-(MAIN_HEADER-Pad33)") (class "Default")
      (node (ref "MAIN_HEADER") (pin "33") (pinfunction "33_33") (pintype "passive"))
    )
    (net (code "97") (name "unconnected-(MAIN_HEADER-Pad34)") (class "Default")
      (node (ref "MAIN_HEADER") (pin "34") (pinfunction "34_34") (pintype "passive"))
    )
    (net (code "98") (name "unconnected-(MAIN_HEADER-Pad35)") (class "Default")
      (node (ref "MAIN_HEADER") (pin "35") (pinfunction "35_35") (pintype "passive"))
    )
    (net (code "99") (name "unconnected-(MAIN_HEADER-Pad36)") (class "Default")
      (node (ref "MAIN_HEADER") (pin "36") (pinfunction "36_36") (pintype "passive"))
    )
    (net (code "100") (name "unconnected-(MAIN_HEADER-Pad37)") (class "Default")
      (node (ref "MAIN_HEADER") (pin "37") (pinfunction "37_37") (pintype "passive"))
    )
    (net (code "101") (name "unconnected-(MAIN_HEADER-Pad38)") (class "Default")
      (node (ref "MAIN_HEADER") (pin "38") (pinfunction "38_38") (pintype "passive"))
    )
    (net (code "102") (name "unconnected-(MAIN_HEADER-Pad39)") (class "Default")
      (node (ref "MAIN_HEADER") (pin "39") (pinfunction "39_39") (pintype "passive"))
    )
    (net (code "103") (name "unconnected-(MAIN_HEADER-Pad40)") (class "Default")
      (node (ref "MAIN_HEADER") (pin "40") (pinfunction "40_40") (pintype "passive"))
    )
    (net (code "104") (name "unconnected-(U$1-A21{slash}DAC0-Pad21{slash}DAC0)") (class "Default")
      (node (ref "U$1") (pin "21/DAC0") (pinfunction "A21/DAC0_21/DAC0") (pintype "bidirectional"))
    )
    (net (code "105") (name "unconnected-(U$1-Pad0{slash}RX)") (class "Default")
      (node (ref "U$1") (pin "0/RX") (pinfunction "0/RX_0/RX") (pintype "bidirectional"))
    )
    (net (code "106") (name "unconnected-(U$1-Pad1{slash}TX)") (class "Default")
      (node (ref "U$1") (pin "1/TX") (pinfunction "1/TX_1/TX") (pintype "bidirectional"))
    )
    (net (code "107") (name "unconnected-(U$1-Pad3V3_LO)") (class "Default")
      (node (ref "U$1") (pin "3V3_LO") (pinfunction "3V3_LO_3V3_LO") (pintype "bidirectional"))
    )
    (net (code "108") (name "unconnected-(U$1-PadA10)") (class "Default")
      (node (ref "U$1") (pin "A10") (pinfunction "A10_A10") (pintype "bidirectional"))
    )
    (net (code "109") (name "unconnected-(U$1-PadA11)") (class "Default")
      (node (ref "U$1") (pin "A11") (pinfunction "A11_A11") (pintype "bidirectional"))
    )
    (net (code "110") (name "unconnected-(U$1-PadAGND)") (class "Default")
      (node (ref "U$1") (pin "AGND") (pinfunction "AGND_AGND") (pintype "bidirectional"))
    )
    (net (code "111") (name "unconnected-(U$1-PadAREF)") (class "Default")
      (node (ref "U$1") (pin "AREF") (pinfunction "AREF_AREF") (pintype "bidirectional"))
    )
    (net (code "112") (name "unconnected-(U$1-PadVIN)") (class "Default")
      (node (ref "U$1") (pin "VIN") (pinfunction "VIN_VIN") (pintype "bidirectional"))
    )
    (net (code "113") (name "unconnected-(U$3-PadGND1)") (class "Default")
      (node (ref "U$3") (pin "GND1") (pinfunction "GND1_GND1") (pintype "bidirectional"))
    )
    (net (code "114") (name "unconnected-(U$3-PadGND2)") (class "Default")
      (node (ref "U$3") (pin "GND2") (pinfunction "GND2_GND2") (pintype "bidirectional"))
    )
    (net (code "115") (name "unconnected-(U$3-PadSTBY)") (class "Default")
      (node (ref "U$3") (pin "STBY") (pinfunction "STBY_STBY") (pintype "bidirectional"))
    )
    (net (code "116") (name "unconnected-(U$5-PadEN)") (class "Default")
      (node (ref "U$5") (pin "EN") (pinfunction "EN_EN") (pintype "bidirectional"))
    )
    (net (code "117") (name "unconnected-(U$6-PadGND_IN2)") (class "Default")
      (node (ref "U$6") (pin "GND_IN2") (pinfunction "GND_IN2_GND_IN2") (pintype "bidirectional"))
    )
    (net (code "118") (name "unconnected-(U$7-PadPG)") (class "Default")
      (node (ref "U$7") (pin "PG") (pinfunction "PG_PG") (pintype "bidirectional"))
    )
    (net (code "119") (name "unconnected-(U$7-VOUT-PadVOUT@2)") (class "Default")
      (node (ref "U$7") (pin "VOUT@2") (pinfunction "VOUT_VOUT@2") (pintype "bidirectional"))
    )
    (net (code "120") (name "unconnected-(U$7-VRP-PadVRP@1)") (class "Default")
      (node (ref "U$7") (pin "VRP@1") (pinfunction "VRP_VRP@1") (pintype "bidirectional"))
    )
    (net (code "121") (name "unconnected-(U$7-VRP-PadVRP@2)") (class "Default")
      (node (ref "U$7") (pin "VRP@2") (pinfunction "VRP_VRP@2") (pintype "bidirectional"))
    )
  )
)
